# working.net
KiCad netlist of a schematic drawn in EAGLE
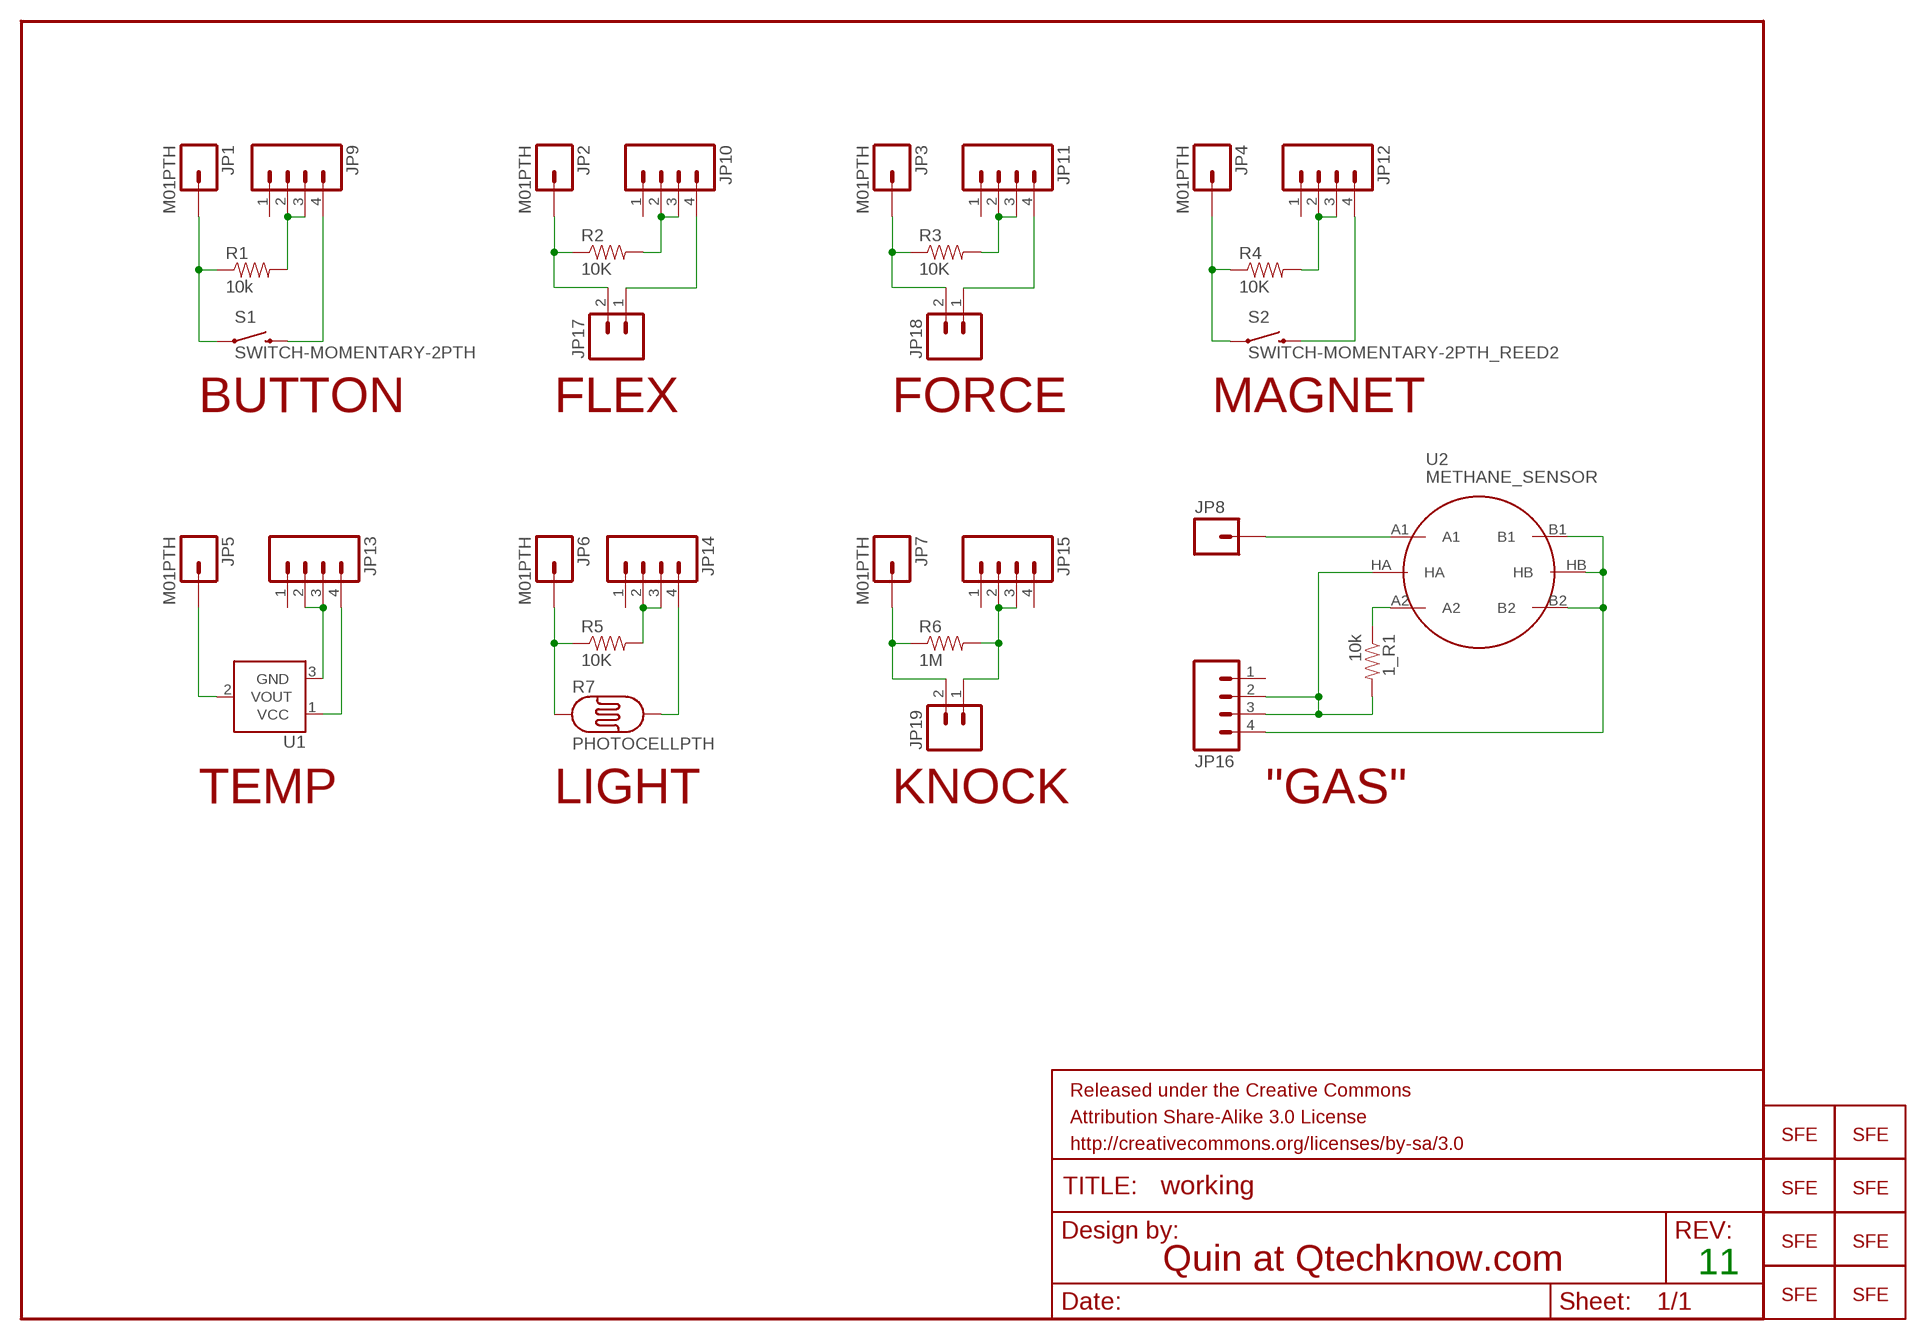
[diagram p0: schematic, sheet 1]

(export (version "E")
  (design (tool "Eeschema 10.0.6"))
  (components
    (comp (ref "1_R1")
      (value "10k")
      (footprint "eagle-import:AXIAL-0.3")
      (libsource (lib "eagle-import") (part "RESISTORAXIAL-0.3"))
    )
    (comp (ref "FRAME1")
      (value "FRAME-LETTER")
      (footprint "eagle-import:CREATIVE_COMMONS")
      (libsource (lib "eagle-import") (part "FRAME-LETTER"))
    )
    (comp (ref "JP1")
      (value "M01PTH")
      (footprint "eagle-import:1X01")
      (libsource (lib "eagle-import") (part "2_1_SFE Connectors_M01PTH"))
    )
    (comp (ref "JP2")
      (value "M01PTH")
      (footprint "eagle-import:1X01")
      (libsource (lib "eagle-import") (part "2_2_SFE Connectors_M01PTH"))
    )
    (comp (ref "JP3")
      (value "M01PTH")
      (footprint "eagle-import:1X01")
      (libsource (lib "eagle-import") (part "2_3_SFE Connectors_M01PTH"))
    )
    (comp (ref "JP4")
      (value "M01PTH")
      (footprint "eagle-import:1X01")
      (libsource (lib "eagle-import") (part "2_6_SFE Connectors_M01PTH"))
    )
    (comp (ref "JP5")
      (value "M01PTH")
      (footprint "eagle-import:1X01")
      (libsource (lib "eagle-import") (part "2_7_SFE Connectors_M01PTH"))
    )
    (comp (ref "JP6")
      (value "M01PTH")
      (footprint "eagle-import:1X01")
      (libsource (lib "eagle-import") (part "2_5_SFE Connectors_M01PTH"))
    )
    (comp (ref "JP7")
      (value "M01PTH")
      (footprint "eagle-import:1X01")
      (libsource (lib "eagle-import") (part "2_4_SFE Connectors_M01PTH"))
    )
    (comp (ref "JP8")
      (value "M01PTH")
      (footprint "eagle-import:1X01")
      (libsource (lib "eagle-import") (part "M01PTH"))
    )
    (comp (ref "JP9")
      (value "M04PTH")
      (footprint "eagle-import:1X04")
      (libsource (lib "eagle-import") (part "2_1_SFE Connectors_M04PTH"))
    )
    (comp (ref "JP10")
      (value "M04PTH")
      (footprint "eagle-import:1X04")
      (libsource (lib "eagle-import") (part "2_2_SFE Connectors_M04PTH"))
    )
    (comp (ref "JP11")
      (value "M04PTH")
      (footprint "eagle-import:1X04")
      (libsource (lib "eagle-import") (part "2_3_SFE Connectors_M04PTH"))
    )
    (comp (ref "JP12")
      (value "M04PTH")
      (footprint "eagle-import:1X04")
      (libsource (lib "eagle-import") (part "2_6_SFE Connectors_M04PTH"))
    )
    (comp (ref "JP13")
      (value "M04PTH")
      (footprint "eagle-import:1X04")
      (libsource (lib "eagle-import") (part "2_7_SFE Connectors_M04PTH"))
    )
    (comp (ref "JP14")
      (value "M04PTH")
      (footprint "eagle-import:1X04")
      (libsource (lib "eagle-import") (part "2_5_SFE Connectors_M04PTH"))
    )
    (comp (ref "JP15")
      (value "M04PTH")
      (footprint "eagle-import:1X04")
      (libsource (lib "eagle-import") (part "2_4_SFE Connectors_M04PTH"))
    )
    (comp (ref "JP16")
      (value "M04PTH")
      (footprint "eagle-import:1X04")
      (libsource (lib "eagle-import") (part "M04PTH"))
    )
    (comp (ref "JP17")
      (value "M02PTH")
      (footprint "eagle-import:1X02")
      (libsource (lib "eagle-import") (part "M02PTH"))
    )
    (comp (ref "JP18")
      (value "M02PTH")
      (footprint "eagle-import:1X02")
      (libsource (lib "eagle-import") (part "2_3_SFE Connectors_M02PTH"))
    )
    (comp (ref "JP19")
      (value "M02PTH")
      (footprint "eagle-import:1X02")
      (libsource (lib "eagle-import") (part "2_4_SFE Connectors_M02PTH"))
    )
    (comp (ref "LOGO1")
      (value "LOGO-SFESK")
      (footprint "eagle-import:SFE-LOGO-FLAME")
      (libsource (lib "eagle-import") (part "LOGO-SFESK"))
    )
    (comp (ref "LOGO2")
      (value "LOGO-SFESK")
      (footprint "eagle-import:SFE-LOGO-FLAME")
      (libsource (lib "eagle-import") (part "LOGO-SFESK"))
    )
    (comp (ref "LOGO3")
      (value "LOGO-SFESK")
      (footprint "eagle-import:SFE-LOGO-FLAME")
      (libsource (lib "eagle-import") (part "LOGO-SFESK"))
    )
    (comp (ref "LOGO4")
      (value "LOGO-SFESK")
      (footprint "eagle-import:SFE-LOGO-FLAME")
      (libsource (lib "eagle-import") (part "LOGO-SFESK"))
    )
    (comp (ref "LOGO5")
      (value "LOGO-SFESK")
      (footprint "eagle-import:SFE-LOGO-FLAME")
      (libsource (lib "eagle-import") (part "LOGO-SFESK"))
    )
    (comp (ref "LOGO6")
      (value "LOGO-SFESK")
      (footprint "eagle-import:SFE-LOGO-FLAME")
      (libsource (lib "eagle-import") (part "LOGO-SFESK"))
    )
    (comp (ref "LOGO7")
      (value "LOGO-SFESK")
      (footprint "eagle-import:SFE-LOGO-FLAME")
      (libsource (lib "eagle-import") (part "LOGO-SFESK"))
    )
    (comp (ref "LOGO8")
      (value "LOGO-SFESK")
      (footprint "eagle-import:SFE-LOGO-FLAME")
      (libsource (lib "eagle-import") (part "LOGO-SFESK"))
    )
    (comp (ref "R1")
      (value "10k")
      (footprint "eagle-import:AXIAL-0.3")
      (libsource (lib "eagle-import") (part "2_1_SFE Passives_RESISTORAXIAL-0.3"))
    )
    (comp (ref "R2")
      (value "10K")
      (footprint "eagle-import:AXIAL-0.3")
      (libsource (lib "eagle-import") (part "2_2_SFE Passives_RESISTORAXIAL-0.3"))
    )
    (comp (ref "R3")
      (value "10K")
      (footprint "eagle-import:AXIAL-0.3")
      (libsource (lib "eagle-import") (part "2_3_SFE Passives_RESISTORAXIAL-0.3"))
    )
    (comp (ref "R4")
      (value "10K")
      (footprint "eagle-import:AXIAL-0.3")
      (libsource (lib "eagle-import") (part "2_6_SFE Passives_RESISTORAXIAL-0.3"))
    )
    (comp (ref "R5")
      (value "10K")
      (footprint "eagle-import:AXIAL-0.3")
      (libsource (lib "eagle-import") (part "2_5_SFE Passives_RESISTORAXIAL-0.3"))
    )
    (comp (ref "R6")
      (value "1M")
      (footprint "eagle-import:AXIAL-0.3")
      (libsource (lib "eagle-import") (part "2_4_SFE Passives_RESISTORAXIAL-0.3"))
    )
    (comp (ref "R7")
      (value "PHOTOCELLPTH")
      (footprint "eagle-import:PHOTOCELL")
      (libsource (lib "eagle-import") (part "PHOTOCELLPTH"))
    )
    (comp (ref "S1")
      (value "SWITCH-MOMENTARY-2PTH")
      (footprint "eagle-import:TACTILE-PTH")
      (libsource (lib "eagle-import") (part "SWITCH-MOMENTARY-2PTH"))
    )
    (comp (ref "S2")
      (value "SWITCH-MOMENTARY-2PTH_REED2")
      (footprint "eagle-import:REED_SWITCH_PLASTIC")
      (libsource (lib "eagle-import") (part "2_6_SFE Electromechanical_SWITCH-MOMENTARY-2PTH_REED2"))
    )
    (comp (ref "U1")
      (value "TMP36GT9")
      (footprint "eagle-import:TO-92")
      (libsource (lib "eagle-import") (part "TMP36GT9"))
    )
    (comp (ref "U2")
      (value "METHANE_SENSOR")
      (footprint "eagle-import:MQ-3")
      (libsource (lib "eagle-import") (part "METHANE_SENSOR"))
    )
  )
  (nets
    (net (code "1") (name "Net-(1_R1-1)") (class "Default")
      (node (ref "1_R1") (pin "P$1") (pinfunction "1_P$1") (pintype "passive"))
      (node (ref "U2") (pin "A2") (pinfunction "A2_A2") (pintype "bidirectional"))
    )
    (net (code "2") (name "Net-(1_R1-2)") (class "Default")
      (node (ref "1_R1") (pin "P$2") (pinfunction "2_P$2") (pintype "passive"))
      (node (ref "JP16") (pin "2") (pinfunction "2_2") (pintype "passive"))
      (node (ref "JP16") (pin "3") (pinfunction "3_3") (pintype "passive"))
      (node (ref "U2") (pin "HA") (pinfunction "HA_HA") (pintype "bidirectional"))
    )
    (net (code "3") (name "Net-(JP8-Pad1)") (class "Default")
      (node (ref "JP8") (pin "1") (pinfunction "1_1") (pintype "passive"))
      (node (ref "U2") (pin "A1") (pinfunction "A1_A1") (pintype "bidirectional"))
    )
    (net (code "4") (name "Net-(JP10-Pad4)") (class "Default")
      (node (ref "JP10") (pin "4") (pinfunction "4_4") (pintype "passive"))
      (node (ref "JP17") (pin "1") (pinfunction "1_1") (pintype "passive"))
    )
    (net (code "5") (name "Net-(JP11-Pad4)") (class "Default")
      (node (ref "JP11") (pin "4") (pinfunction "4_4") (pintype "passive"))
      (node (ref "JP18") (pin "1") (pinfunction "1_1") (pintype "passive"))
    )
    (net (code "6") (name "Net-(JP16-Pad4)") (class "Default")
      (node (ref "JP16") (pin "4") (pinfunction "4_4") (pintype "passive"))
      (node (ref "U2") (pin "B1") (pinfunction "B1_B1") (pintype "bidirectional"))
      (node (ref "U2") (pin "B2") (pinfunction "B2_B2") (pintype "bidirectional"))
      (node (ref "U2") (pin "HB") (pinfunction "HB_HB") (pintype "bidirectional"))
    )
    (net (code "7") (name "Net-(R1-1)") (class "Default")
      (node (ref "JP1") (pin "1") (pinfunction "1_1") (pintype "passive"))
      (node (ref "R1") (pin "P$1") (pinfunction "1_P$1") (pintype "passive"))
      (node (ref "S1") (pin "1") (pinfunction "1_1") (pintype "passive"))
    )
    (net (code "8") (name "Net-(R1-2)") (class "Default")
      (node (ref "JP9") (pin "2") (pinfunction "2_2") (pintype "passive"))
      (node (ref "JP9") (pin "3") (pinfunction "3_3") (pintype "passive"))
      (node (ref "R1") (pin "P$2") (pinfunction "2_P$2") (pintype "passive"))
    )
    (net (code "9") (name "Net-(R2-1)") (class "Default")
      (node (ref "JP17") (pin "2") (pinfunction "2_2") (pintype "passive"))
      (node (ref "JP2") (pin "1") (pinfunction "1_1") (pintype "passive"))
      (node (ref "R2") (pin "P$1") (pinfunction "1_P$1") (pintype "passive"))
    )
    (net (code "10") (name "Net-(R2-2)") (class "Default")
      (node (ref "JP10") (pin "2") (pinfunction "2_2") (pintype "passive"))
      (node (ref "JP10") (pin "3") (pinfunction "3_3") (pintype "passive"))
      (node (ref "R2") (pin "P$2") (pinfunction "2_P$2") (pintype "passive"))
    )
    (net (code "11") (name "Net-(R3-1)") (class "Default")
      (node (ref "JP18") (pin "2") (pinfunction "2_2") (pintype "passive"))
      (node (ref "JP3") (pin "1") (pinfunction "1_1") (pintype "passive"))
      (node (ref "R3") (pin "P$1") (pinfunction "1_P$1") (pintype "passive"))
    )
    (net (code "12") (name "Net-(R3-2)") (class "Default")
      (node (ref "JP11") (pin "2") (pinfunction "2_2") (pintype "passive"))
      (node (ref "JP11") (pin "3") (pinfunction "3_3") (pintype "passive"))
      (node (ref "R3") (pin "P$2") (pinfunction "2_P$2") (pintype "passive"))
    )
    (net (code "13") (name "Net-(R4-1)") (class "Default")
      (node (ref "JP4") (pin "1") (pinfunction "1_1") (pintype "passive"))
      (node (ref "R4") (pin "P$1") (pinfunction "1_P$1") (pintype "passive"))
      (node (ref "S2") (pin "P$1") (pinfunction "1_P$1") (pintype "passive"))
    )
    (net (code "14") (name "Net-(R4-2)") (class "Default")
      (node (ref "JP12") (pin "2") (pinfunction "2_2") (pintype "passive"))
      (node (ref "JP12") (pin "3") (pinfunction "3_3") (pintype "passive"))
      (node (ref "R4") (pin "P$2") (pinfunction "2_P$2") (pintype "passive"))
    )
    (net (code "15") (name "Net-(R5-1)") (class "Default")
      (node (ref "JP6") (pin "1") (pinfunction "1_1") (pintype "passive"))
      (node (ref "R5") (pin "P$1") (pinfunction "1_P$1") (pintype "passive"))
      (node (ref "R7") (pin "1") (pinfunction "P$1_1") (pintype "bidirectional"))
    )
    (net (code "16") (name "Net-(R5-2)") (class "Default")
      (node (ref "JP14") (pin "2") (pinfunction "2_2") (pintype "passive"))
      (node (ref "JP14") (pin "3") (pinfunction "3_3") (pintype "passive"))
      (node (ref "R5") (pin "P$2") (pinfunction "2_P$2") (pintype "passive"))
    )
    (net (code "17") (name "Net-(R6-1)") (class "Default")
      (node (ref "JP19") (pin "2") (pinfunction "2_2") (pintype "passive"))
      (node (ref "JP7") (pin "1") (pinfunction "1_1") (pintype "passive"))
      (node (ref "R6") (pin "P$1") (pinfunction "1_P$1") (pintype "passive"))
    )
    (net (code "18") (name "Net-(R6-2)") (class "Default")
      (node (ref "JP15") (pin "2") (pinfunction "2_2") (pintype "passive"))
      (node (ref "JP15") (pin "3") (pinfunction "3_3") (pintype "passive"))
      (node (ref "JP19") (pin "1") (pinfunction "1_1") (pintype "passive"))
      (node (ref "R6") (pin "P$2") (pinfunction "2_P$2") (pintype "passive"))
    )
    (net (code "19") (name "Net-(R7-P$2)") (class "Default")
      (node (ref "JP14") (pin "4") (pinfunction "4_4") (pintype "passive"))
      (node (ref "R7") (pin "2") (pinfunction "P$2_2") (pintype "bidirectional"))
    )
    (net (code "20") (name "Net-(S1-2)") (class "Default")
      (node (ref "JP9") (pin "4") (pinfunction "4_4") (pintype "passive"))
      (node (ref "S1") (pin "3") (pinfunction "2_3") (pintype "passive"))
    )
    (net (code "21") (name "Net-(S2-2)") (class "Default")
      (node (ref "JP12") (pin "4") (pinfunction "4_4") (pintype "passive"))
      (node (ref "S2") (pin "P$2") (pinfunction "2_P$2") (pintype "passive"))
    )
    (net (code "22") (name "Net-(U1-GND)") (class "Default")
      (node (ref "JP13") (pin "2") (pinfunction "2_2") (pintype "passive"))
      (node (ref "JP13") (pin "3") (pinfunction "3_3") (pintype "passive"))
      (node (ref "U1") (pin "3") (pinfunction "GND_3") (pintype "bidirectional"))
    )
    (net (code "23") (name "Net-(U1-VCC)") (class "Default")
      (node (ref "JP13") (pin "4") (pinfunction "4_4") (pintype "passive"))
      (node (ref "U1") (pin "1") (pinfunction "VCC_1") (pintype "bidirectional"))
    )
    (net (code "24") (name "Net-(U1-VOUT)") (class "Default")
      (node (ref "JP5") (pin "1") (pinfunction "1_1") (pintype "passive"))
      (node (ref "U1") (pin "2") (pinfunction "VOUT_2") (pintype "bidirectional"))
    )
    (net (code "25") (name "unconnected-(JP9-Pad1)") (class "Default")
      (node (ref "JP9") (pin "1") (pinfunction "1_1") (pintype "passive"))
    )
    (net (code "26") (name "unconnected-(JP10-Pad1)") (class "Default")
      (node (ref "JP10") (pin "1") (pinfunction "1_1") (pintype "passive"))
    )
    (net (code "27") (name "unconnected-(JP11-Pad1)") (class "Default")
      (node (ref "JP11") (pin "1") (pinfunction "1_1") (pintype "passive"))
    )
    (net (code "28") (name "unconnected-(JP12-Pad1)") (class "Default")
      (node (ref "JP12") (pin "1") (pinfunction "1_1") (pintype "passive"))
    )
    (net (code "29") (name "unconnected-(JP13-Pad1)") (class "Default")
      (node (ref "JP13") (pin "1") (pinfunction "1_1") (pintype "passive"))
    )
    (net (code "30") (name "unconnected-(JP14-Pad1)") (class "Default")
      (node (ref "JP14") (pin "1") (pinfunction "1_1") (pintype "passive"))
    )
    (net (code "31") (name "unconnected-(JP15-Pad1)") (class "Default")
      (node (ref "JP15") (pin "1") (pinfunction "1_1") (pintype "passive"))
    )
    (net (code "32") (name "unconnected-(JP15-Pad4)") (class "Default")
      (node (ref "JP15") (pin "4") (pinfunction "4_4") (pintype "passive"))
    )
    (net (code "33") (name "unconnected-(JP16-Pad1)") (class "Default")
      (node (ref "JP16") (pin "1") (pinfunction "1_1") (pintype "passive"))
    )
  )
)
